# MCU_Board_V1_2_1.net
KiCad netlist of a schematic drawn in EAGLE
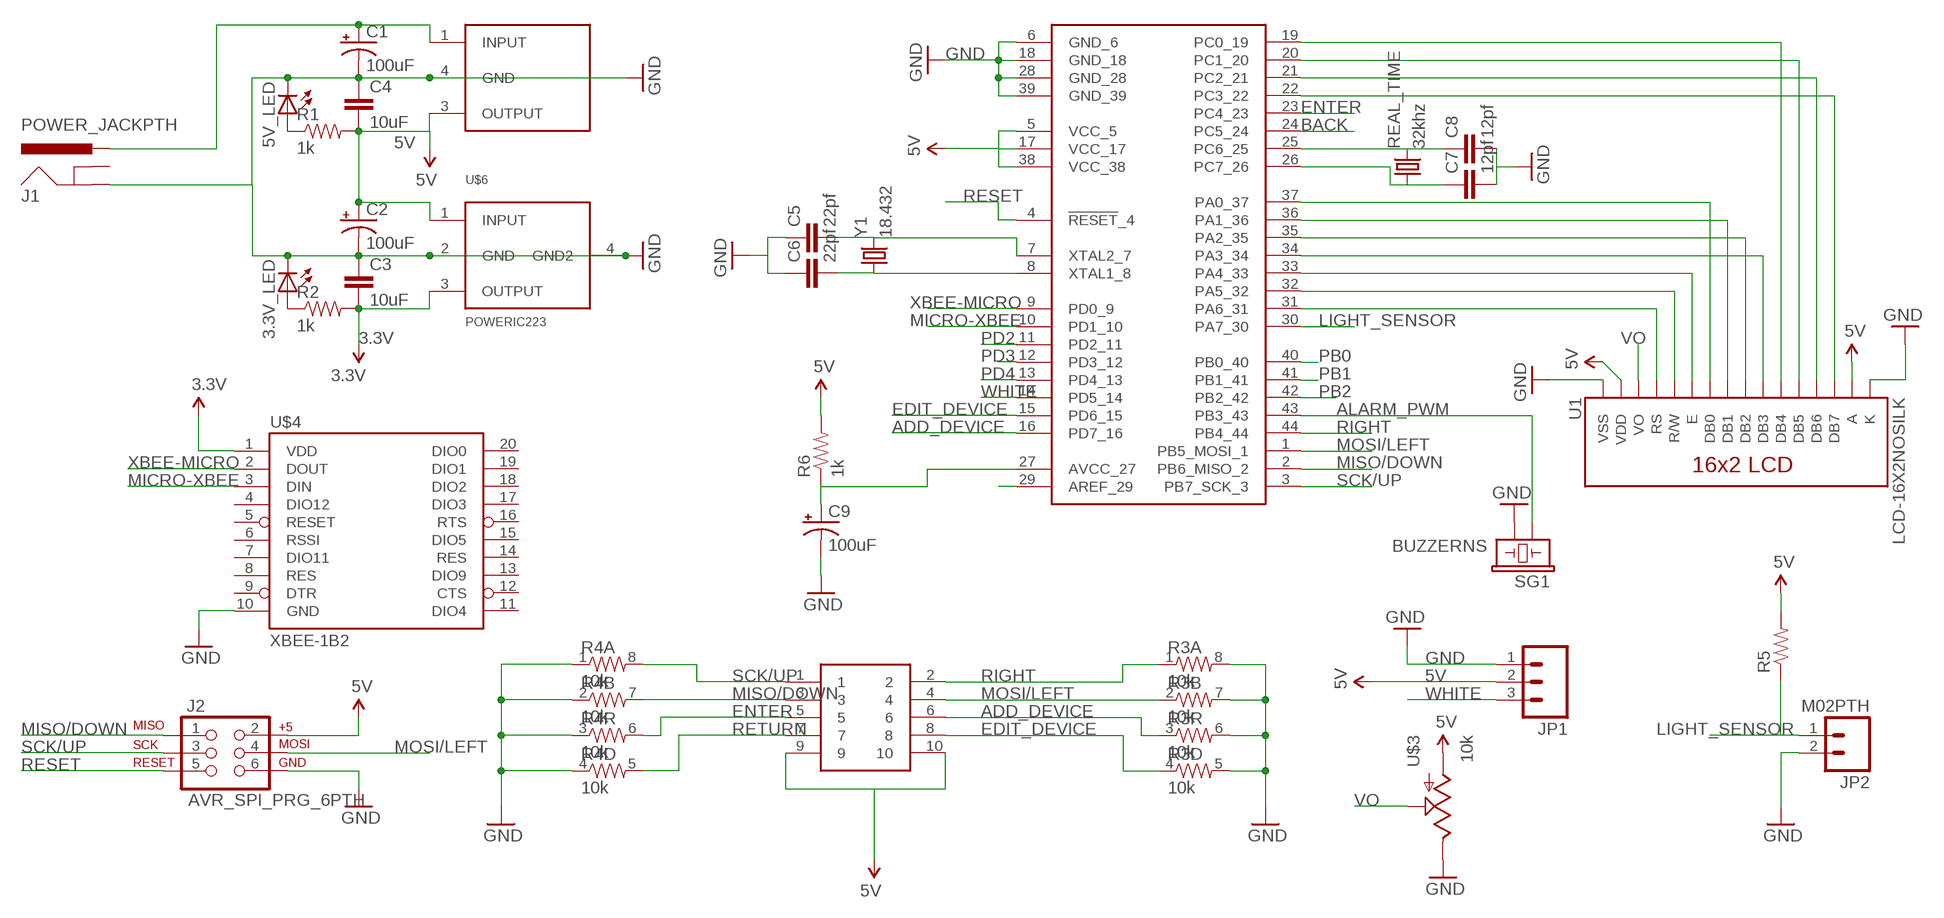
[diagram p0: schematic, sheet 1]

(export (version "E")
  (design (tool "Eeschema 10.0.6"))
  (components
    (comp (ref "3.3V_LED")
      (value "LED1206")
      (footprint "eagle-import:LED-1206")
      (libsource (lib "eagle-import") (part "LED1206"))
    )
    (comp (ref "5V_LED")
      (value "LED1206")
      (footprint "eagle-import:LED-1206")
      (libsource (lib "eagle-import") (part "LED1206"))
    )
    (comp (ref "C1")
      (value "100uF")
      (footprint "eagle-import:PANASONIC_D")
      (libsource (lib "eagle-import") (part "CAP_POLD"))
    )
    (comp (ref "C2")
      (value "100uF")
      (footprint "eagle-import:PANASONIC_D")
      (libsource (lib "eagle-import") (part "CAP_POLD"))
    )
    (comp (ref "C3")
      (value "10uF")
      (footprint "eagle-import:1206")
      (libsource (lib "eagle-import") (part "CAP1206"))
    )
    (comp (ref "C4")
      (value "10uF")
      (footprint "eagle-import:1206")
      (libsource (lib "eagle-import") (part "CAP1206"))
    )
    (comp (ref "C5")
      (value "22pf")
      (footprint "eagle-import:0805")
      (libsource (lib "eagle-import") (part "CAP0805"))
    )
    (comp (ref "C6")
      (value "22pf")
      (footprint "eagle-import:0805")
      (libsource (lib "eagle-import") (part "CAP0805"))
    )
    (comp (ref "C7")
      (value "12pf")
      (footprint "eagle-import:0805")
      (libsource (lib "eagle-import") (part "SparkFun-Passives_CAP0805"))
    )
    (comp (ref "C8")
      (value "12pf")
      (footprint "eagle-import:0805")
      (libsource (lib "eagle-import") (part "SparkFun-Passives_CAP0805"))
    )
    (comp (ref "C9")
      (value "100uF")
      (footprint "eagle-import:PANASONIC_D")
      (libsource (lib "eagle-import") (part "CAP_POLD"))
    )
    (comp (ref "J1")
      (value "POWER_JACKPTH")
      (footprint "eagle-import:POWER_JACK_PTH")
      (libsource (lib "eagle-import") (part "POWER_JACKPTH"))
    )
    (comp (ref "J2")
      (value "AVR_SPI_PRG_6PTH")
      (footprint "eagle-import:2X3")
      (libsource (lib "eagle-import") (part "AVR_SPI_PRG_6PTH"))
    )
    (comp (ref "JP1")
      (value "M03PTH")
      (footprint "eagle-import:1X03")
      (libsource (lib "eagle-import") (part "M03PTH"))
    )
    (comp (ref "JP2")
      (value "M02PTH")
      (footprint "eagle-import:1X02")
      (libsource (lib "eagle-import") (part "M02PTH"))
    )
    (comp (ref "R1")
      (value "1k")
      (footprint "eagle-import:1206")
      (libsource (lib "eagle-import") (part "RESISTOR1206"))
    )
    (comp (ref "R2")
      (value "1k")
      (footprint "eagle-import:1206")
      (libsource (lib "eagle-import") (part "RESISTOR1206"))
    )
    (comp (ref "R3")
      (value "10k")
      (footprint "eagle-import:0603-ARV")
      (libsource (lib "eagle-import") (part "RESISTOR-ARRAY0603-ARV"))
    )
    (comp (ref "R4")
      (value "10k")
      (footprint "eagle-import:0603-ARV")
      (libsource (lib "eagle-import") (part "RESISTOR-ARRAY0603-ARV"))
    )
    (comp (ref "R5")
      (value "RESISTOR1206")
      (footprint "eagle-import:1206")
      (libsource (lib "eagle-import") (part "RESISTOR1206"))
    )
    (comp (ref "R6")
      (value "1k")
      (footprint "eagle-import:1206")
      (libsource (lib "eagle-import") (part "RESISTOR1206"))
    )
    (comp (ref "REAL_TIME")
      (value "32khz")
      (footprint "eagle-import:TC26H")
      (libsource (lib "eagle-import") (part "CRYSTALTC26H"))
    )
    (comp (ref "SG1")
      (value "BUZZERNS")
      (footprint "eagle-import:BUZZER-12MM-NS")
      (libsource (lib "eagle-import") (part "BUZZERNS"))
    )
    (comp (ref "U$1")
      (value "ATMEGA1284")
      (footprint "eagle-import:TQFP44")
      (libsource (lib "eagle-import") (part "ATMEGA1284"))
    )
    (comp (ref "U$2")
      (value "10PIN_HEADER_MALETHROUGH-HOLE")
      (footprint "eagle-import:2X5-SHROUDED")
      (libsource (lib "eagle-import") (part "10PIN_HEADER_MALETHROUGH-HOLE"))
    )
    (comp (ref "U$3")
      (value "10k")
      (footprint "eagle-import:TRIM_POT")
      (libsource (lib "eagle-import") (part "POTTRIM"))
    )
    (comp (ref "U$4")
      (value "XBEE-1B2")
      (footprint "eagle-import:XBEE-SILK")
      (libsource (lib "eagle-import") (part "XBEE-1B2"))
    )
    (comp (ref "U$5")
      (value "DPACK_V_REG")
      (footprint "eagle-import:DPAK")
      (libsource (lib "eagle-import") (part "DPACK_V_REG"))
    )
    (comp (ref "U$6")
      (value "POWERIC223")
      (footprint "eagle-import:SOT223")
      (libsource (lib "eagle-import") (part "POWERIC223"))
    )
    (comp (ref "U1")
      (value "LCD-16X2NOSILK")
      (footprint "eagle-import:LCD-16X2_NOSILK")
      (libsource (lib "eagle-import") (part "LCD-16X2NOSILK"))
    )
    (comp (ref "Y1")
      (value "18.432")
      (footprint "eagle-import:HC49US")
      (libsource (lib "eagle-import") (part "CRYSTALHC49US"))
    )
  )
  (nets
    (net (code "1") (name "/ADD_DEVICE") (class "Default")
      (node (ref "R3") (pin "3") (pinfunction "1_3") (pintype "passive"))
      (node (ref "U$1") (pin "16") (pinfunction "PD7_16_16") (pintype "bidirectional"))
      (node (ref "U$2") (pin "6") (pinfunction "6_6") (pintype "bidirectional"))
    )
    (net (code "2") (name "/ALARM_PWM") (class "Default")
      (node (ref "SG1") (pin "+") (pinfunction "1_+") (pintype "passive"))
      (node (ref "U$1") (pin "43") (pinfunction "PB3_43_43") (pintype "bidirectional"))
    )
    (net (code "3") (name "/BACK") (class "Default")
      (node (ref "U$1") (pin "24") (pinfunction "PC5_24_24") (pintype "bidirectional"))
    )
    (net (code "4") (name "/EDIT_DEVICE") (class "Default")
      (node (ref "R3") (pin "4") (pinfunction "1_4") (pintype "passive"))
      (node (ref "U$1") (pin "15") (pinfunction "PD6_15_15") (pintype "bidirectional"))
      (node (ref "U$2") (pin "8") (pinfunction "8_8") (pintype "bidirectional"))
    )
    (net (code "5") (name "/ENTER") (class "Default")
      (node (ref "R4") (pin "6") (pinfunction "2_6") (pintype "passive"))
      (node (ref "U$1") (pin "23") (pinfunction "PC4_23_23") (pintype "bidirectional"))
      (node (ref "U$2") (pin "5") (pinfunction "5_5") (pintype "bidirectional"))
    )
    (net (code "6") (name "/LIGHT_SENSOR") (class "Default")
      (node (ref "JP2") (pin "1") (pinfunction "1_1") (pintype "passive"))
      (node (ref "R5") (pin "1") (pinfunction "1_1") (pintype "passive"))
      (node (ref "U$1") (pin "30") (pinfunction "PA7_30_30") (pintype "bidirectional"))
    )
    (net (code "7") (name "/MICRO-XBEE") (class "Default")
      (node (ref "U$1") (pin "10") (pinfunction "PD1_10_10") (pintype "bidirectional"))
      (node (ref "U$4") (pin "3") (pinfunction "DIN_3") (pintype "input"))
    )
    (net (code "8") (name "/MISO{slash}DOWN") (class "Default")
      (node (ref "J2") (pin "1") (pinfunction "1_1") (pintype "passive"))
      (node (ref "R4") (pin "7") (pinfunction "2_7") (pintype "passive"))
      (node (ref "U$1") (pin "2") (pinfunction "PB6_MISO_2_2") (pintype "bidirectional"))
      (node (ref "U$2") (pin "3") (pinfunction "3_3") (pintype "bidirectional"))
    )
    (net (code "9") (name "/MOSI{slash}LEFT") (class "Default")
      (node (ref "J2") (pin "4") (pinfunction "4_4") (pintype "passive"))
      (node (ref "R3") (pin "2") (pinfunction "1_2") (pintype "passive"))
      (node (ref "U$1") (pin "1") (pinfunction "PB5_MOSI_1_1") (pintype "bidirectional"))
      (node (ref "U$2") (pin "4") (pinfunction "4_4") (pintype "bidirectional"))
    )
    (net (code "10") (name "/PB0") (class "Default")
      (node (ref "U$1") (pin "40") (pinfunction "PB0_40_40") (pintype "bidirectional"))
    )
    (net (code "11") (name "/PB1") (class "Default")
      (node (ref "U$1") (pin "41") (pinfunction "PB1_41_41") (pintype "bidirectional"))
    )
    (net (code "12") (name "/PB2") (class "Default")
      (node (ref "U$1") (pin "42") (pinfunction "PB2_42_42") (pintype "bidirectional"))
    )
    (net (code "13") (name "/PD2") (class "Default")
      (node (ref "U$1") (pin "11") (pinfunction "PD2_11_11") (pintype "bidirectional"))
    )
    (net (code "14") (name "/PD3") (class "Default")
      (node (ref "U$1") (pin "12") (pinfunction "PD3_12_12") (pintype "bidirectional"))
    )
    (net (code "15") (name "/PD4") (class "Default")
      (node (ref "U$1") (pin "13") (pinfunction "PD4_13_13") (pintype "bidirectional"))
    )
    (net (code "16") (name "/RESET") (class "Default")
      (node (ref "J2") (pin "5") (pinfunction "5_5") (pintype "passive"))
      (node (ref "U$1") (pin "4") (pinfunction "~{RESET}_4_4") (pintype "bidirectional"))
    )
    (net (code "17") (name "/RETURN") (class "Default")
      (node (ref "R4") (pin "5") (pinfunction "2_5") (pintype "passive"))
      (node (ref "U$2") (pin "7") (pinfunction "7_7") (pintype "bidirectional"))
    )
    (net (code "18") (name "/RIGHT") (class "Default")
      (node (ref "R3") (pin "1") (pinfunction "1_1") (pintype "passive"))
      (node (ref "U$1") (pin "44") (pinfunction "PB4_44_44") (pintype "bidirectional"))
      (node (ref "U$2") (pin "2") (pinfunction "2_2") (pintype "bidirectional"))
    )
    (net (code "19") (name "/SCK{slash}UP") (class "Default")
      (node (ref "J2") (pin "3") (pinfunction "3_3") (pintype "passive"))
      (node (ref "R4") (pin "8") (pinfunction "2_8") (pintype "passive"))
      (node (ref "U$1") (pin "3") (pinfunction "PB7_SCK_3_3") (pintype "bidirectional"))
      (node (ref "U$2") (pin "1") (pinfunction "1_1") (pintype "bidirectional"))
    )
    (net (code "20") (name "/VO") (class "Default")
      (node (ref "U$3") (pin "1") (pinfunction "S_1") (pintype "passive"))
      (node (ref "U1") (pin "3") (pinfunction "VO_3") (pintype "bidirectional"))
    )
    (net (code "21") (name "/WHITE") (class "Default")
      (node (ref "JP1") (pin "3") (pinfunction "3_3") (pintype "passive"))
      (node (ref "U$1") (pin "14") (pinfunction "PD5_14_14") (pintype "bidirectional"))
    )
    (net (code "22") (name "/XBEE-MICRO") (class "Default")
      (node (ref "U$1") (pin "9") (pinfunction "PD0_9_9") (pintype "bidirectional"))
      (node (ref "U$4") (pin "2") (pinfunction "DOUT_2") (pintype "output"))
    )
    (net (code "23") (name "3.3V") (class "Default")
      (node (ref "C3") (pin "2") (pinfunction "2_2") (pintype "passive"))
      (node (ref "R2") (pin "2") (pinfunction "2_2") (pintype "passive"))
      (node (ref "U$4") (pin "1") (pinfunction "VDD_1") (pintype "power_in"))
      (node (ref "U$6") (pin "3") (pinfunction "OUTPUT_3") (pintype "bidirectional"))
    )
    (net (code "24") (name "5V") (class "Default")
      (node (ref "C2") (pin "+") (pinfunction "+_+") (pintype "passive"))
      (node (ref "C4") (pin "2") (pinfunction "2_2") (pintype "passive"))
      (node (ref "J2") (pin "2") (pinfunction "2_2") (pintype "passive"))
      (node (ref "JP1") (pin "2") (pinfunction "2_2") (pintype "passive"))
      (node (ref "R1") (pin "2") (pinfunction "2_2") (pintype "passive"))
      (node (ref "R5") (pin "2") (pinfunction "2_2") (pintype "passive"))
      (node (ref "R6") (pin "2") (pinfunction "2_2") (pintype "passive"))
      (node (ref "U$1") (pin "17") (pinfunction "VCC_17_17") (pintype "bidirectional"))
      (node (ref "U$1") (pin "38") (pinfunction "VCC_38_38") (pintype "bidirectional"))
      (node (ref "U$1") (pin "5") (pinfunction "VCC_5_5") (pintype "bidirectional"))
      (node (ref "U$2") (pin "10") (pinfunction "10_10") (pintype "bidirectional"))
      (node (ref "U$2") (pin "9") (pinfunction "9_9") (pintype "bidirectional"))
      (node (ref "U$3") (pin "3") (pinfunction "A_3") (pintype "passive"))
      (node (ref "U$5") (pin "3") (pinfunction "OUTPUT_3") (pintype "bidirectional"))
      (node (ref "U$6") (pin "1") (pinfunction "INPUT_1") (pintype "bidirectional"))
      (node (ref "U1") (pin "15") (pinfunction "A_15") (pintype "power_in"))
      (node (ref "U1") (pin "2") (pinfunction "VDD_2") (pintype "power_in"))
    )
    (net (code "25") (name "GND") (class "Default")
      (node (ref "3.3V_LED") (pin "C") (pinfunction "C_C") (pintype "passive"))
      (node (ref "5V_LED") (pin "C") (pinfunction "C_C") (pintype "passive"))
      (node (ref "C1") (pin "-") (pinfunction "-_-") (pintype "passive"))
      (node (ref "C2") (pin "-") (pinfunction "-_-") (pintype "passive"))
      (node (ref "C3") (pin "1") (pinfunction "1_1") (pintype "passive"))
      (node (ref "C4") (pin "1") (pinfunction "1_1") (pintype "passive"))
      (node (ref "C5") (pin "1") (pinfunction "1_1") (pintype "passive"))
      (node (ref "C6") (pin "1") (pinfunction "1_1") (pintype "passive"))
      (node (ref "C7") (pin "2") (pinfunction "2_2") (pintype "passive"))
      (node (ref "C8") (pin "2") (pinfunction "2_2") (pintype "passive"))
      (node (ref "C9") (pin "-") (pinfunction "-_-") (pintype "passive"))
      (node (ref "J1") (pin "GND") (pinfunction "GND_GND") (pintype "bidirectional"))
      (node (ref "J2") (pin "6") (pinfunction "6_6") (pintype "passive"))
      (node (ref "JP1") (pin "1") (pinfunction "1_1") (pintype "passive"))
      (node (ref "JP2") (pin "2") (pinfunction "2_2") (pintype "passive"))
      (node (ref "R3") (pin "5") (pinfunction "2_5") (pintype "passive"))
      (node (ref "R3") (pin "6") (pinfunction "2_6") (pintype "passive"))
      (node (ref "R3") (pin "7") (pinfunction "2_7") (pintype "passive"))
      (node (ref "R3") (pin "8") (pinfunction "2_8") (pintype "passive"))
      (node (ref "R4") (pin "1") (pinfunction "1_1") (pintype "passive"))
      (node (ref "R4") (pin "2") (pinfunction "1_2") (pintype "passive"))
      (node (ref "R4") (pin "3") (pinfunction "1_3") (pintype "passive"))
      (node (ref "R4") (pin "4") (pinfunction "1_4") (pintype "passive"))
      (node (ref "SG1") (pin "-") (pinfunction "2_-") (pintype "passive"))
      (node (ref "U$1") (pin "18") (pinfunction "GND_18_18") (pintype "bidirectional"))
      (node (ref "U$1") (pin "28") (pinfunction "GND_28_28") (pintype "bidirectional"))
      (node (ref "U$1") (pin "39") (pinfunction "GND_39_39") (pintype "bidirectional"))
      (node (ref "U$1") (pin "6") (pinfunction "GND_6_6") (pintype "bidirectional"))
      (node (ref "U$3") (pin "2") (pinfunction "E_2") (pintype "passive"))
      (node (ref "U$4") (pin "10") (pinfunction "GND_10") (pintype "power_in"))
      (node (ref "U$5") (pin "4") (pinfunction "GND_4") (pintype "bidirectional"))
      (node (ref "U$6") (pin "2") (pinfunction "GND_2") (pintype "bidirectional"))
      (node (ref "U$6") (pin "4") (pinfunction "GND2_4") (pintype "bidirectional"))
      (node (ref "U1") (pin "1") (pinfunction "VSS_1") (pintype "power_in"))
      (node (ref "U1") (pin "16") (pinfunction "K_16") (pintype "power_in"))
    )
    (net (code "26") (name "Net-(3.3V_LED-PadA)") (class "Default")
      (node (ref "3.3V_LED") (pin "A") (pinfunction "A_A") (pintype "passive"))
      (node (ref "R2") (pin "1") (pinfunction "1_1") (pintype "passive"))
    )
    (net (code "27") (name "Net-(5V_LED-PadA)") (class "Default")
      (node (ref "5V_LED") (pin "A") (pinfunction "A_A") (pintype "passive"))
      (node (ref "R1") (pin "1") (pinfunction "1_1") (pintype "passive"))
    )
    (net (code "28") (name "Net-(U$1-AVCC_27)") (class "Default")
      (node (ref "C9") (pin "+") (pinfunction "+_+") (pintype "passive"))
      (node (ref "R6") (pin "1") (pinfunction "1_1") (pintype "passive"))
      (node (ref "U$1") (pin "27") (pinfunction "AVCC_27_27") (pintype "bidirectional"))
    )
    (net (code "29") (name "Net-(U$1-PA0_37)") (class "Default")
      (node (ref "U$1") (pin "37") (pinfunction "PA0_37_37") (pintype "bidirectional"))
      (node (ref "U1") (pin "7") (pinfunction "DB0_7") (pintype "bidirectional"))
    )
    (net (code "30") (name "Net-(U$1-PA1_36)") (class "Default")
      (node (ref "U$1") (pin "36") (pinfunction "PA1_36_36") (pintype "bidirectional"))
      (node (ref "U1") (pin "8") (pinfunction "DB1_8") (pintype "bidirectional"))
    )
    (net (code "31") (name "Net-(U$1-PA2_35)") (class "Default")
      (node (ref "U$1") (pin "35") (pinfunction "PA2_35_35") (pintype "bidirectional"))
      (node (ref "U1") (pin "9") (pinfunction "DB2_9") (pintype "bidirectional"))
    )
    (net (code "32") (name "Net-(U$1-PA3_34)") (class "Default")
      (node (ref "U$1") (pin "34") (pinfunction "PA3_34_34") (pintype "bidirectional"))
      (node (ref "U1") (pin "10") (pinfunction "DB3_10") (pintype "bidirectional"))
    )
    (net (code "33") (name "Net-(U$1-PA4_33)") (class "Default")
      (node (ref "U$1") (pin "33") (pinfunction "PA4_33_33") (pintype "bidirectional"))
      (node (ref "U1") (pin "6") (pinfunction "E_6") (pintype "input"))
    )
    (net (code "34") (name "Net-(U$1-PA5_32)") (class "Default")
      (node (ref "U$1") (pin "32") (pinfunction "PA5_32_32") (pintype "bidirectional"))
      (node (ref "U1") (pin "5") (pinfunction "R/W_5") (pintype "input"))
    )
    (net (code "35") (name "Net-(U$1-PA6_31)") (class "Default")
      (node (ref "U$1") (pin "31") (pinfunction "PA6_31_31") (pintype "bidirectional"))
      (node (ref "U1") (pin "4") (pinfunction "RS_4") (pintype "input"))
    )
    (net (code "36") (name "Net-(U$1-PC0_19)") (class "Default")
      (node (ref "U$1") (pin "19") (pinfunction "PC0_19_19") (pintype "bidirectional"))
      (node (ref "U1") (pin "11") (pinfunction "DB4_11") (pintype "bidirectional"))
    )
    (net (code "37") (name "Net-(U$1-PC1_20)") (class "Default")
      (node (ref "U$1") (pin "20") (pinfunction "PC1_20_20") (pintype "bidirectional"))
      (node (ref "U1") (pin "12") (pinfunction "DB5_12") (pintype "bidirectional"))
    )
    (net (code "38") (name "Net-(U$1-PC2_21)") (class "Default")
      (node (ref "U$1") (pin "21") (pinfunction "PC2_21_21") (pintype "bidirectional"))
      (node (ref "U1") (pin "13") (pinfunction "DB6_13") (pintype "bidirectional"))
    )
    (net (code "39") (name "Net-(U$1-PC3_22)") (class "Default")
      (node (ref "U$1") (pin "22") (pinfunction "PC3_22_22") (pintype "bidirectional"))
      (node (ref "U1") (pin "14") (pinfunction "DB7_14") (pintype "bidirectional"))
    )
    (net (code "40") (name "Net-(U$1-PC6_25)") (class "Default")
      (node (ref "C8") (pin "1") (pinfunction "1_1") (pintype "passive"))
      (node (ref "REAL_TIME") (pin "2") (pinfunction "2_2") (pintype "passive"))
      (node (ref "U$1") (pin "25") (pinfunction "PC6_25_25") (pintype "bidirectional"))
    )
    (net (code "41") (name "Net-(U$1-PC7_26)") (class "Default")
      (node (ref "C7") (pin "1") (pinfunction "1_1") (pintype "passive"))
      (node (ref "REAL_TIME") (pin "1") (pinfunction "1_1") (pintype "passive"))
      (node (ref "U$1") (pin "26") (pinfunction "PC7_26_26") (pintype "bidirectional"))
    )
    (net (code "42") (name "Net-(U$1-XTAL1_8)") (class "Default")
      (node (ref "C6") (pin "2") (pinfunction "2_2") (pintype "passive"))
      (node (ref "U$1") (pin "8") (pinfunction "XTAL1_8_8") (pintype "bidirectional"))
      (node (ref "Y1") (pin "1") (pinfunction "1_1") (pintype "passive"))
    )
    (net (code "43") (name "Net-(U$1-XTAL2_7)") (class "Default")
      (node (ref "C5") (pin "2") (pinfunction "2_2") (pintype "passive"))
      (node (ref "U$1") (pin "7") (pinfunction "XTAL2_7_7") (pintype "bidirectional"))
      (node (ref "Y1") (pin "2") (pinfunction "2_2") (pintype "passive"))
    )
    (net (code "44") (name "Net-(U$5-INPUT)") (class "Default")
      (node (ref "C1") (pin "+") (pinfunction "+_+") (pintype "passive"))
      (node (ref "J1") (pin "PWR") (pinfunction "PWR_PWR") (pintype "bidirectional"))
      (node (ref "U$5") (pin "1") (pinfunction "INPUT_1") (pintype "bidirectional"))
    )
    (net (code "45") (name "unconnected-(J1-PadGNDBREAK)") (class "Default")
      (node (ref "J1") (pin "GNDBREAK") (pinfunction "GNDBREAK_GNDBREAK") (pintype "bidirectional"))
    )
    (net (code "46") (name "unconnected-(U$1-AREF_29-Pad29)") (class "Default")
      (node (ref "U$1") (pin "29") (pinfunction "AREF_29_29") (pintype "bidirectional"))
    )
    (net (code "47") (name "unconnected-(U$4-CTS-Pad12)") (class "Default")
      (node (ref "U$4") (pin "12") (pinfunction "CTS_12") (pintype "output"))
    )
    (net (code "48") (name "unconnected-(U$4-DIO0-Pad20)") (class "Default")
      (node (ref "U$4") (pin "20") (pinfunction "DIO0_20") (pintype "bidirectional"))
    )
    (net (code "49") (name "unconnected-(U$4-DIO1-Pad19)") (class "Default")
      (node (ref "U$4") (pin "19") (pinfunction "DIO1_19") (pintype "bidirectional"))
    )
    (net (code "50") (name "unconnected-(U$4-DIO2-Pad18)") (class "Default")
      (node (ref "U$4") (pin "18") (pinfunction "DIO2_18") (pintype "bidirectional"))
    )
    (net (code "51") (name "unconnected-(U$4-DIO3-Pad17)") (class "Default")
      (node (ref "U$4") (pin "17") (pinfunction "DIO3_17") (pintype "bidirectional"))
    )
    (net (code "52") (name "unconnected-(U$4-DIO4-Pad11)") (class "Default")
      (node (ref "U$4") (pin "11") (pinfunction "DIO4_11") (pintype "bidirectional"))
    )
    (net (code "53") (name "unconnected-(U$4-DIO5-Pad15)") (class "Default")
      (node (ref "U$4") (pin "15") (pinfunction "DIO5_15") (pintype "bidirectional"))
    )
    (net (code "54") (name "unconnected-(U$4-DIO9-Pad13)") (class "Default")
      (node (ref "U$4") (pin "13") (pinfunction "DIO9_13") (pintype "bidirectional"))
    )
    (net (code "55") (name "unconnected-(U$4-DIO11-Pad7)") (class "Default")
      (node (ref "U$4") (pin "7") (pinfunction "DIO11_7") (pintype "bidirectional"))
    )
    (net (code "56") (name "unconnected-(U$4-DIO12-Pad4)") (class "Default")
      (node (ref "U$4") (pin "4") (pinfunction "DIO12_4") (pintype "bidirectional"))
    )
    (net (code "57") (name "unconnected-(U$4-DTR-Pad9)") (class "Default")
      (node (ref "U$4") (pin "9") (pinfunction "DTR_9") (pintype "bidirectional"))
    )
    (net (code "58") (name "unconnected-(U$4-RES-Pad8)") (class "Default")
      (node (ref "U$4") (pin "8") (pinfunction "RES_8") (pintype "bidirectional"))
    )
    (net (code "59") (name "unconnected-(U$4-RES-Pad14)") (class "Default")
      (node (ref "U$4") (pin "14") (pinfunction "RES_14") (pintype "bidirectional"))
    )
    (net (code "60") (name "unconnected-(U$4-RESET-Pad5)") (class "Default")
      (node (ref "U$4") (pin "5") (pinfunction "RESET_5") (pintype "input"))
    )
    (net (code "61") (name "unconnected-(U$4-RSSI-Pad6)") (class "Default")
      (node (ref "U$4") (pin "6") (pinfunction "RSSI_6") (pintype "bidirectional"))
    )
    (net (code "62") (name "unconnected-(U$4-RTS-Pad16)") (class "Default")
      (node (ref "U$4") (pin "16") (pinfunction "RTS_16") (pintype "input"))
    )
  )
)
